# EEGbreakoutREVB.net
KiCad netlist of a schematic drawn in EAGLE
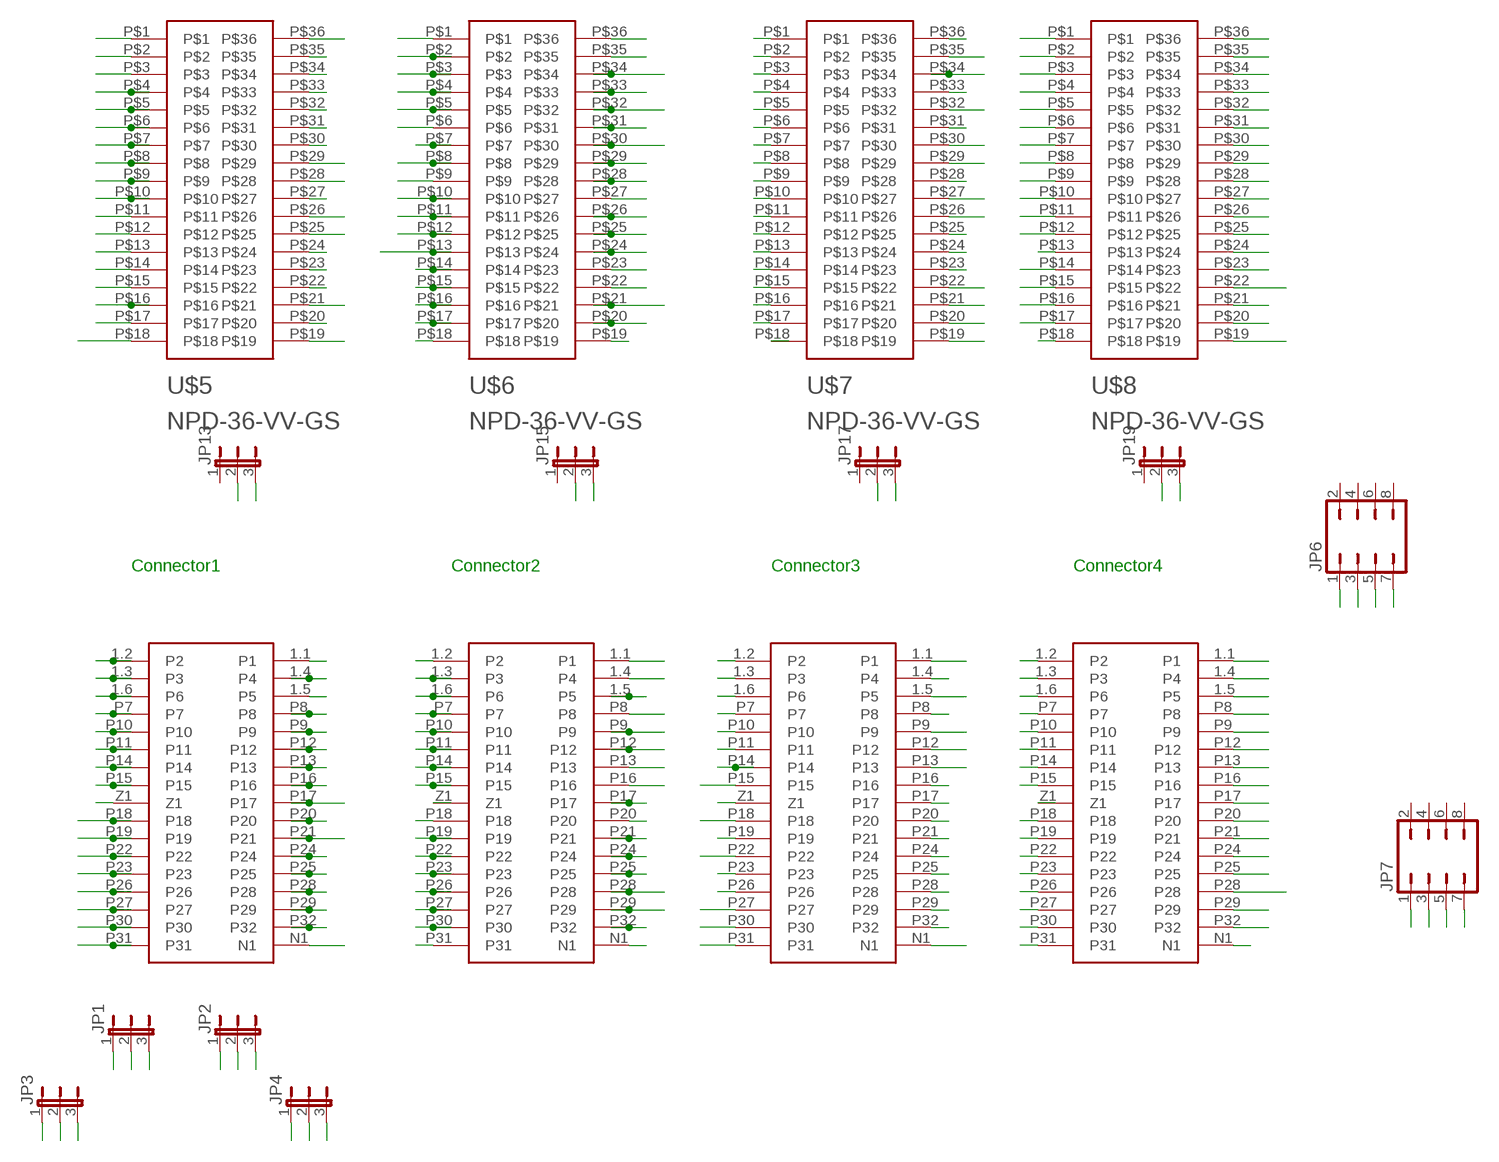
[diagram p0: schematic, sheet 1]

(export (version "E")
  (design (tool "Eeschema 10.0.6"))
  (components
    (comp (ref "JP1")
      (value "JP2E")
      (footprint "eagle-import:JP2")
      (libsource (lib "eagle-import") (part "JP2E"))
    )
    (comp (ref "JP2")
      (value "JP2E")
      (footprint "eagle-import:JP2")
      (libsource (lib "eagle-import") (part "JP2E"))
    )
    (comp (ref "JP3")
      (value "JP2E")
      (footprint "eagle-import:JP2")
      (libsource (lib "eagle-import") (part "JP2E"))
    )
    (comp (ref "JP4")
      (value "JP2E")
      (footprint "eagle-import:JP2")
      (libsource (lib "eagle-import") (part "JP2E"))
    )
    (comp (ref "JP6")
      (value "JP4Q")
      (footprint "eagle-import:JP4Q")
      (libsource (lib "eagle-import") (part "JP4Q"))
    )
    (comp (ref "JP7")
      (value "JP4Q")
      (footprint "eagle-import:JP4Q")
      (libsource (lib "eagle-import") (part "JP4Q"))
    )
    (comp (ref "JP13")
      (value "JP2E")
      (footprint "eagle-import:JP2")
      (libsource (lib "eagle-import") (part "JP2E"))
    )
    (comp (ref "JP15")
      (value "JP2E")
      (footprint "eagle-import:JP2")
      (libsource (lib "eagle-import") (part "JP2E"))
    )
    (comp (ref "JP17")
      (value "JP2E")
      (footprint "eagle-import:JP2")
      (libsource (lib "eagle-import") (part "JP2E"))
    )
    (comp (ref "JP19")
      (value "JP2E")
      (footprint "eagle-import:JP2")
      (libsource (lib "eagle-import") (part "JP2E"))
    )
    (comp (ref "U$1")
      (value "P50")
      (footprint "eagle-import:CON-MOLEX_71061-0003SM")
      (libsource (lib "eagle-import") (part "P50"))
    )
    (comp (ref "U$2")
      (value "P50")
      (footprint "eagle-import:CON-MOLEX_71061-0003SM")
      (libsource (lib "eagle-import") (part "P50"))
    )
    (comp (ref "U$3")
      (value "P50")
      (footprint "eagle-import:CON-MOLEX_71061-0003SM")
      (libsource (lib "eagle-import") (part "P50"))
    )
    (comp (ref "U$4")
      (value "P50")
      (footprint "eagle-import:CON-MOLEX_71061-0003SM")
      (libsource (lib "eagle-import") (part "P50"))
    )
    (comp (ref "U$5")
      (value "NPD-36-VV-GS")
      (footprint "eagle-import:NPD-36-VV-GS")
      (libsource (lib "eagle-import") (part "NPD-36-VV-GS"))
    )
    (comp (ref "U$6")
      (value "NPD-36-VV-GS")
      (footprint "eagle-import:NPD-36-VV-GS")
      (libsource (lib "eagle-import") (part "NPD-36-VV-GS"))
    )
    (comp (ref "U$7")
      (value "NPD-36-VV-GS")
      (footprint "eagle-import:NPD-36-VV-GS")
      (libsource (lib "eagle-import") (part "NPD-36-VV-GS"))
    )
    (comp (ref "U$8")
      (value "NPD-36-VV-GS")
      (footprint "eagle-import:NPD-36-VV-GS")
      (libsource (lib "eagle-import") (part "NPD-36-VV-GS"))
    )
  )
  (nets
    (net (code "1") (name "/1.1") (class "Default")
      (node (ref "U$1") (pin "1.1") (pinfunction "P1_1.1") (pintype "bidirectional"))
      (node (ref "U$5") (pin "P$2") (pinfunction "P$2_P$2") (pintype "bidirectional"))
    )
    (net (code "2") (name "/1.2") (class "Default")
      (node (ref "U$1") (pin "1.4") (pinfunction "P4_1.4") (pintype "bidirectional"))
      (node (ref "U$5") (pin "P$3") (pinfunction "P$3_P$3") (pintype "bidirectional"))
    )
    (net (code "3") (name "/1.3") (class "Default")
      (node (ref "U$1") (pin "1.5") (pinfunction "P5_1.5") (pintype "bidirectional"))
      (node (ref "U$5") (pin "P$4") (pinfunction "P$4_P$4") (pintype "bidirectional"))
    )
    (net (code "4") (name "/1.4") (class "Default")
      (node (ref "U$1") (pin "P8") (pinfunction "P8_P8") (pintype "bidirectional"))
      (node (ref "U$5") (pin "P$5") (pinfunction "P$5_P$5") (pintype "bidirectional"))
    )
    (net (code "5") (name "/1.5") (class "Default")
      (node (ref "U$1") (pin "P9") (pinfunction "P9_P9") (pintype "bidirectional"))
      (node (ref "U$5") (pin "P$6") (pinfunction "P$6_P$6") (pintype "bidirectional"))
    )
    (net (code "6") (name "/1.6") (class "Default")
      (node (ref "U$1") (pin "P12") (pinfunction "P12_P12") (pintype "bidirectional"))
      (node (ref "U$5") (pin "P$7") (pinfunction "P$7_P$7") (pintype "bidirectional"))
    )
    (net (code "7") (name "/1.7") (class "Default")
      (node (ref "U$1") (pin "P13") (pinfunction "P13_P13") (pintype "bidirectional"))
      (node (ref "U$5") (pin "P$8") (pinfunction "P$8_P$8") (pintype "bidirectional"))
    )
    (net (code "8") (name "/1.8") (class "Default")
      (node (ref "U$1") (pin "P16") (pinfunction "P16_P16") (pintype "bidirectional"))
      (node (ref "U$5") (pin "P$9") (pinfunction "P$9_P$9") (pintype "bidirectional"))
    )
    (net (code "9") (name "/1.9") (class "Default")
      (node (ref "U$1") (pin "P17") (pinfunction "P17_P17") (pintype "bidirectional"))
      (node (ref "U$5") (pin "P$10") (pinfunction "P$10_P$10") (pintype "bidirectional"))
    )
    (net (code "10") (name "/1.10") (class "Default")
      (node (ref "U$1") (pin "P20") (pinfunction "P20_P20") (pintype "bidirectional"))
      (node (ref "U$5") (pin "P$11") (pinfunction "P$11_P$11") (pintype "bidirectional"))
    )
    (net (code "11") (name "/1.11") (class "Default")
      (node (ref "U$1") (pin "P21") (pinfunction "P21_P21") (pintype "bidirectional"))
      (node (ref "U$5") (pin "P$12") (pinfunction "P$12_P$12") (pintype "bidirectional"))
    )
    (net (code "12") (name "/1.12") (class "Default")
      (node (ref "U$1") (pin "P24") (pinfunction "P24_P24") (pintype "bidirectional"))
      (node (ref "U$5") (pin "P$13") (pinfunction "P$13_P$13") (pintype "bidirectional"))
    )
    (net (code "13") (name "/1.13") (class "Default")
      (node (ref "U$1") (pin "P25") (pinfunction "P25_P25") (pintype "bidirectional"))
      (node (ref "U$5") (pin "P$14") (pinfunction "P$14_P$14") (pintype "bidirectional"))
    )
    (net (code "14") (name "/1.14") (class "Default")
      (node (ref "U$1") (pin "P28") (pinfunction "P28_P28") (pintype "bidirectional"))
      (node (ref "U$5") (pin "P$15") (pinfunction "P$15_P$15") (pintype "bidirectional"))
    )
    (net (code "15") (name "/1.15") (class "Default")
      (node (ref "U$1") (pin "P29") (pinfunction "P29_P29") (pintype "bidirectional"))
      (node (ref "U$5") (pin "P$16") (pinfunction "P$16_P$16") (pintype "bidirectional"))
    )
    (net (code "16") (name "/1.16") (class "Default")
      (node (ref "U$1") (pin "P32") (pinfunction "P32_P32") (pintype "bidirectional"))
      (node (ref "U$5") (pin "P$17") (pinfunction "P$17_P$17") (pintype "bidirectional"))
    )
    (net (code "17") (name "/1.17") (class "Default")
      (node (ref "U$1") (pin "1.2") (pinfunction "P2_1.2") (pintype "bidirectional"))
      (node (ref "U$5") (pin "P$20") (pinfunction "P$20_P$20") (pintype "bidirectional"))
    )
    (net (code "18") (name "/1.18") (class "Default")
      (node (ref "U$1") (pin "1.3") (pinfunction "P3_1.3") (pintype "bidirectional"))
      (node (ref "U$5") (pin "P$21") (pinfunction "P$21_P$21") (pintype "bidirectional"))
    )
    (net (code "19") (name "/1.20") (class "Default")
      (node (ref "U$1") (pin "P7") (pinfunction "P7_P7") (pintype "bidirectional"))
      (node (ref "U$5") (pin "P$23") (pinfunction "P$23_P$23") (pintype "bidirectional"))
    )
    (net (code "20") (name "/1.21") (class "Default")
      (node (ref "U$1") (pin "P10") (pinfunction "P10_P10") (pintype "bidirectional"))
      (node (ref "U$5") (pin "P$24") (pinfunction "P$24_P$24") (pintype "bidirectional"))
    )
    (net (code "21") (name "/1.22") (class "Default")
      (node (ref "U$1") (pin "P11") (pinfunction "P11_P11") (pintype "bidirectional"))
      (node (ref "U$5") (pin "P$25") (pinfunction "P$25_P$25") (pintype "bidirectional"))
    )
    (net (code "22") (name "/1.23") (class "Default")
      (node (ref "U$1") (pin "P14") (pinfunction "P14_P14") (pintype "bidirectional"))
      (node (ref "U$5") (pin "P$26") (pinfunction "P$26_P$26") (pintype "bidirectional"))
    )
    (net (code "23") (name "/1.24") (class "Default")
      (node (ref "U$1") (pin "P15") (pinfunction "P15_P15") (pintype "bidirectional"))
      (node (ref "U$5") (pin "P$27") (pinfunction "P$27_P$27") (pintype "bidirectional"))
    )
    (net (code "24") (name "/1.25") (class "Default")
      (node (ref "U$1") (pin "P18") (pinfunction "P18_P18") (pintype "bidirectional"))
      (node (ref "U$5") (pin "P$28") (pinfunction "P$28_P$28") (pintype "bidirectional"))
    )
    (net (code "25") (name "/1.26") (class "Default")
      (node (ref "U$1") (pin "P19") (pinfunction "P19_P19") (pintype "bidirectional"))
      (node (ref "U$5") (pin "P$29") (pinfunction "P$29_P$29") (pintype "bidirectional"))
    )
    (net (code "26") (name "/1.27") (class "Default")
      (node (ref "U$1") (pin "P22") (pinfunction "P22_P22") (pintype "bidirectional"))
      (node (ref "U$5") (pin "P$30") (pinfunction "P$30_P$30") (pintype "bidirectional"))
    )
    (net (code "27") (name "/1.28") (class "Default")
      (node (ref "U$1") (pin "P23") (pinfunction "P23_P23") (pintype "bidirectional"))
      (node (ref "U$5") (pin "P$31") (pinfunction "P$31_P$31") (pintype "bidirectional"))
    )
    (net (code "28") (name "/1.29") (class "Default")
      (node (ref "JP4") (pin "2") (pinfunction "2_2") (pintype "passive"))
      (node (ref "U$5") (pin "P$32") (pinfunction "P$32_P$32") (pintype "bidirectional"))
    )
    (net (code "29") (name "/1.30") (class "Default")
      (node (ref "JP2") (pin "2") (pinfunction "2_2") (pintype "passive"))
      (node (ref "U$5") (pin "P$33") (pinfunction "P$33_P$33") (pintype "bidirectional"))
    )
    (net (code "30") (name "/1.31") (class "Default")
      (node (ref "JP1") (pin "2") (pinfunction "2_2") (pintype "passive"))
      (node (ref "U$5") (pin "P$34") (pinfunction "P$34_P$34") (pintype "bidirectional"))
    )
    (net (code "31") (name "/1.32") (class "Default")
      (node (ref "JP3") (pin "2") (pinfunction "2_2") (pintype "passive"))
      (node (ref "U$5") (pin "P$35") (pinfunction "P$35_P$35") (pintype "bidirectional"))
    )
    (net (code "32") (name "/2.1") (class "Default")
      (node (ref "U$2") (pin "1.1") (pinfunction "P1_1.1") (pintype "bidirectional"))
      (node (ref "U$6") (pin "P$2") (pinfunction "P$2_P$2") (pintype "bidirectional"))
    )
    (net (code "33") (name "/2.2") (class "Default")
      (node (ref "U$2") (pin "1.4") (pinfunction "P4_1.4") (pintype "bidirectional"))
      (node (ref "U$6") (pin "P$3") (pinfunction "P$3_P$3") (pintype "bidirectional"))
    )
    (net (code "34") (name "/2.3") (class "Default")
      (node (ref "U$2") (pin "1.5") (pinfunction "P5_1.5") (pintype "bidirectional"))
      (node (ref "U$6") (pin "P$4") (pinfunction "P$4_P$4") (pintype "bidirectional"))
    )
    (net (code "35") (name "/2.4") (class "Default")
      (node (ref "U$2") (pin "P8") (pinfunction "P8_P8") (pintype "bidirectional"))
      (node (ref "U$6") (pin "P$5") (pinfunction "P$5_P$5") (pintype "bidirectional"))
    )
    (net (code "36") (name "/2.5") (class "Default")
      (node (ref "U$2") (pin "P9") (pinfunction "P9_P9") (pintype "bidirectional"))
      (node (ref "U$6") (pin "P$6") (pinfunction "P$6_P$6") (pintype "bidirectional"))
    )
    (net (code "37") (name "/2.6") (class "Default")
      (node (ref "U$2") (pin "P12") (pinfunction "P12_P12") (pintype "bidirectional"))
      (node (ref "U$6") (pin "P$7") (pinfunction "P$7_P$7") (pintype "bidirectional"))
    )
    (net (code "38") (name "/2.7") (class "Default")
      (node (ref "U$2") (pin "P13") (pinfunction "P13_P13") (pintype "bidirectional"))
      (node (ref "U$6") (pin "P$8") (pinfunction "P$8_P$8") (pintype "bidirectional"))
    )
    (net (code "39") (name "/2.8") (class "Default")
      (node (ref "U$2") (pin "P16") (pinfunction "P16_P16") (pintype "bidirectional"))
      (node (ref "U$6") (pin "P$9") (pinfunction "P$9_P$9") (pintype "bidirectional"))
    )
    (net (code "40") (name "/2.9") (class "Default")
      (node (ref "U$2") (pin "P17") (pinfunction "P17_P17") (pintype "bidirectional"))
      (node (ref "U$6") (pin "P$10") (pinfunction "P$10_P$10") (pintype "bidirectional"))
    )
    (net (code "41") (name "/2.10") (class "Default")
      (node (ref "U$2") (pin "P20") (pinfunction "P20_P20") (pintype "bidirectional"))
      (node (ref "U$6") (pin "P$11") (pinfunction "P$11_P$11") (pintype "bidirectional"))
    )
    (net (code "42") (name "/2.11") (class "Default")
      (node (ref "U$2") (pin "P21") (pinfunction "P21_P21") (pintype "bidirectional"))
      (node (ref "U$6") (pin "P$12") (pinfunction "P$12_P$12") (pintype "bidirectional"))
    )
    (net (code "43") (name "/2.12") (class "Default")
      (node (ref "U$2") (pin "P24") (pinfunction "P24_P24") (pintype "bidirectional"))
      (node (ref "U$6") (pin "P$13") (pinfunction "P$13_P$13") (pintype "bidirectional"))
    )
    (net (code "44") (name "/2.13") (class "Default")
      (node (ref "U$2") (pin "P25") (pinfunction "P25_P25") (pintype "bidirectional"))
      (node (ref "U$6") (pin "P$14") (pinfunction "P$14_P$14") (pintype "bidirectional"))
    )
    (net (code "45") (name "/2.14") (class "Default")
      (node (ref "U$2") (pin "P28") (pinfunction "P28_P28") (pintype "bidirectional"))
      (node (ref "U$6") (pin "P$15") (pinfunction "P$15_P$15") (pintype "bidirectional"))
    )
    (net (code "46") (name "/2.15") (class "Default")
      (node (ref "U$2") (pin "P29") (pinfunction "P29_P29") (pintype "bidirectional"))
      (node (ref "U$6") (pin "P$16") (pinfunction "P$16_P$16") (pintype "bidirectional"))
    )
    (net (code "47") (name "/2.16") (class "Default")
      (node (ref "U$2") (pin "P32") (pinfunction "P32_P32") (pintype "bidirectional"))
      (node (ref "U$6") (pin "P$17") (pinfunction "P$17_P$17") (pintype "bidirectional"))
    )
    (net (code "48") (name "/2.17") (class "Default")
      (node (ref "U$2") (pin "1.2") (pinfunction "P2_1.2") (pintype "bidirectional"))
      (node (ref "U$6") (pin "P$20") (pinfunction "P$20_P$20") (pintype "bidirectional"))
    )
    (net (code "49") (name "/2.18") (class "Default")
      (node (ref "U$2") (pin "1.3") (pinfunction "P3_1.3") (pintype "bidirectional"))
      (node (ref "U$6") (pin "P$21") (pinfunction "P$21_P$21") (pintype "bidirectional"))
    )
    (net (code "50") (name "/2.19") (class "Default")
      (node (ref "U$2") (pin "1.6") (pinfunction "P6_1.6") (pintype "bidirectional"))
      (node (ref "U$6") (pin "P$22") (pinfunction "P$22_P$22") (pintype "bidirectional"))
    )
    (net (code "51") (name "/2.20") (class "Default")
      (node (ref "U$2") (pin "P7") (pinfunction "P7_P7") (pintype "bidirectional"))
      (node (ref "U$6") (pin "P$23") (pinfunction "P$23_P$23") (pintype "bidirectional"))
    )
    (net (code "52") (name "/2.21") (class "Default")
      (node (ref "U$2") (pin "P10") (pinfunction "P10_P10") (pintype "bidirectional"))
      (node (ref "U$6") (pin "P$24") (pinfunction "P$24_P$24") (pintype "bidirectional"))
    )
    (net (code "53") (name "/2.22") (class "Default")
      (node (ref "U$2") (pin "P11") (pinfunction "P11_P11") (pintype "bidirectional"))
      (node (ref "U$6") (pin "P$25") (pinfunction "P$25_P$25") (pintype "bidirectional"))
    )
    (net (code "54") (name "/2.23") (class "Default")
      (node (ref "U$2") (pin "P14") (pinfunction "P14_P14") (pintype "bidirectional"))
      (node (ref "U$6") (pin "P$26") (pinfunction "P$26_P$26") (pintype "bidirectional"))
    )
    (net (code "55") (name "/2.24") (class "Default")
      (node (ref "U$2") (pin "P15") (pinfunction "P15_P15") (pintype "bidirectional"))
      (node (ref "U$6") (pin "P$27") (pinfunction "P$27_P$27") (pintype "bidirectional"))
    )
    (net (code "56") (name "/2.25") (class "Default")
      (node (ref "U$2") (pin "P18") (pinfunction "P18_P18") (pintype "bidirectional"))
      (node (ref "U$6") (pin "P$28") (pinfunction "P$28_P$28") (pintype "bidirectional"))
    )
    (net (code "57") (name "/2.26") (class "Default")
      (node (ref "U$2") (pin "P19") (pinfunction "P19_P19") (pintype "bidirectional"))
      (node (ref "U$6") (pin "P$29") (pinfunction "P$29_P$29") (pintype "bidirectional"))
    )
    (net (code "58") (name "/2.27") (class "Default")
      (node (ref "U$2") (pin "P22") (pinfunction "P22_P22") (pintype "bidirectional"))
      (node (ref "U$6") (pin "P$30") (pinfunction "P$30_P$30") (pintype "bidirectional"))
    )
    (net (code "59") (name "/2.28") (class "Default")
      (node (ref "U$2") (pin "P23") (pinfunction "P23_P23") (pintype "bidirectional"))
      (node (ref "U$6") (pin "P$31") (pinfunction "P$31_P$31") (pintype "bidirectional"))
    )
    (net (code "60") (name "/2.29") (class "Default")
      (node (ref "U$2") (pin "P26") (pinfunction "P26_P26") (pintype "bidirectional"))
      (node (ref "U$6") (pin "P$32") (pinfunction "P$32_P$32") (pintype "bidirectional"))
    )
    (net (code "61") (name "/2.30") (class "Default")
      (node (ref "U$2") (pin "P27") (pinfunction "P27_P27") (pintype "bidirectional"))
      (node (ref "U$6") (pin "P$33") (pinfunction "P$33_P$33") (pintype "bidirectional"))
    )
    (net (code "62") (name "/2.31") (class "Default")
      (node (ref "U$2") (pin "P30") (pinfunction "P30_P30") (pintype "bidirectional"))
      (node (ref "U$6") (pin "P$34") (pinfunction "P$34_P$34") (pintype "bidirectional"))
    )
    (net (code "63") (name "/2.32") (class "Default")
      (node (ref "U$2") (pin "P31") (pinfunction "P31_P31") (pintype "bidirectional"))
      (node (ref "U$6") (pin "P$35") (pinfunction "P$35_P$35") (pintype "bidirectional"))
    )
    (net (code "64") (name "/3.1") (class "Default")
      (node (ref "U$3") (pin "1.1") (pinfunction "P1_1.1") (pintype "bidirectional"))
      (node (ref "U$7") (pin "P$2") (pinfunction "P$2_P$2") (pintype "bidirectional"))
    )
    (net (code "65") (name "/3.2") (class "Default")
      (node (ref "U$3") (pin "1.4") (pinfunction "P4_1.4") (pintype "bidirectional"))
      (node (ref "U$7") (pin "P$3") (pinfunction "P$3_P$3") (pintype "bidirectional"))
    )
    (net (code "66") (name "/3.3") (class "Default")
      (node (ref "U$3") (pin "1.5") (pinfunction "P5_1.5") (pintype "bidirectional"))
      (node (ref "U$7") (pin "P$4") (pinfunction "P$4_P$4") (pintype "bidirectional"))
    )
    (net (code "67") (name "/3.4") (class "Default")
      (node (ref "U$3") (pin "P8") (pinfunction "P8_P8") (pintype "bidirectional"))
      (node (ref "U$7") (pin "P$5") (pinfunction "P$5_P$5") (pintype "bidirectional"))
    )
    (net (code "68") (name "/3.5") (class "Default")
      (node (ref "U$3") (pin "P9") (pinfunction "P9_P9") (pintype "bidirectional"))
      (node (ref "U$7") (pin "P$6") (pinfunction "P$6_P$6") (pintype "bidirectional"))
    )
    (net (code "69") (name "/3.6") (class "Default")
      (node (ref "U$3") (pin "P12") (pinfunction "P12_P12") (pintype "bidirectional"))
      (node (ref "U$7") (pin "P$7") (pinfunction "P$7_P$7") (pintype "bidirectional"))
    )
    (net (code "70") (name "/3.7") (class "Default")
      (node (ref "U$3") (pin "P13") (pinfunction "P13_P13") (pintype "bidirectional"))
      (node (ref "U$7") (pin "P$8") (pinfunction "P$8_P$8") (pintype "bidirectional"))
    )
    (net (code "71") (name "/3.8") (class "Default")
      (node (ref "U$3") (pin "P16") (pinfunction "P16_P16") (pintype "bidirectional"))
      (node (ref "U$7") (pin "P$9") (pinfunction "P$9_P$9") (pintype "bidirectional"))
    )
    (net (code "72") (name "/3.9") (class "Default")
      (node (ref "U$3") (pin "P17") (pinfunction "P17_P17") (pintype "bidirectional"))
      (node (ref "U$7") (pin "P$10") (pinfunction "P$10_P$10") (pintype "bidirectional"))
    )
    (net (code "73") (name "/3.10") (class "Default")
      (node (ref "U$3") (pin "P20") (pinfunction "P20_P20") (pintype "bidirectional"))
      (node (ref "U$7") (pin "P$11") (pinfunction "P$11_P$11") (pintype "bidirectional"))
    )
    (net (code "74") (name "/3.11") (class "Default")
      (node (ref "U$3") (pin "P21") (pinfunction "P21_P21") (pintype "bidirectional"))
      (node (ref "U$7") (pin "P$12") (pinfunction "P$12_P$12") (pintype "bidirectional"))
    )
    (net (code "75") (name "/3.12") (class "Default")
      (node (ref "U$3") (pin "P24") (pinfunction "P24_P24") (pintype "bidirectional"))
      (node (ref "U$7") (pin "P$13") (pinfunction "P$13_P$13") (pintype "bidirectional"))
    )
    (net (code "76") (name "/3.13") (class "Default")
      (node (ref "U$3") (pin "P25") (pinfunction "P25_P25") (pintype "bidirectional"))
      (node (ref "U$7") (pin "P$14") (pinfunction "P$14_P$14") (pintype "bidirectional"))
    )
    (net (code "77") (name "/3.14") (class "Default")
      (node (ref "U$3") (pin "P28") (pinfunction "P28_P28") (pintype "bidirectional"))
      (node (ref "U$7") (pin "P$15") (pinfunction "P$15_P$15") (pintype "bidirectional"))
    )
    (net (code "78") (name "/3.15") (class "Default")
      (node (ref "U$3") (pin "P29") (pinfunction "P29_P29") (pintype "bidirectional"))
      (node (ref "U$7") (pin "P$16") (pinfunction "P$16_P$16") (pintype "bidirectional"))
    )
    (net (code "79") (name "/3.16") (class "Default")
      (node (ref "U$3") (pin "P32") (pinfunction "P32_P32") (pintype "bidirectional"))
      (node (ref "U$7") (pin "P$17") (pinfunction "P$17_P$17") (pintype "bidirectional"))
    )
    (net (code "80") (name "/3.17") (class "Default")
      (node (ref "U$3") (pin "1.2") (pinfunction "P2_1.2") (pintype "bidirectional"))
      (node (ref "U$7") (pin "P$20") (pinfunction "P$20_P$20") (pintype "bidirectional"))
    )
    (net (code "81") (name "/3.18") (class "Default")
      (node (ref "U$3") (pin "1.3") (pinfunction "P3_1.3") (pintype "bidirectional"))
      (node (ref "U$7") (pin "P$21") (pinfunction "P$21_P$21") (pintype "bidirectional"))
    )
    (net (code "82") (name "/3.19") (class "Default")
      (node (ref "U$3") (pin "1.6") (pinfunction "P6_1.6") (pintype "bidirectional"))
      (node (ref "U$7") (pin "P$22") (pinfunction "P$22_P$22") (pintype "bidirectional"))
    )
    (net (code "83") (name "/3.20") (class "Default")
      (node (ref "U$3") (pin "P7") (pinfunction "P7_P7") (pintype "bidirectional"))
      (node (ref "U$7") (pin "P$23") (pinfunction "P$23_P$23") (pintype "bidirectional"))
    )
    (net (code "84") (name "/3.21") (class "Default")
      (node (ref "U$3") (pin "P10") (pinfunction "P10_P10") (pintype "bidirectional"))
      (node (ref "U$7") (pin "P$24") (pinfunction "P$24_P$24") (pintype "bidirectional"))
    )
    (net (code "85") (name "/3.22") (class "Default")
      (node (ref "U$3") (pin "P11") (pinfunction "P11_P11") (pintype "bidirectional"))
      (node (ref "U$7") (pin "P$25") (pinfunction "P$25_P$25") (pintype "bidirectional"))
    )
    (net (code "86") (name "/3.23") (class "Default")
      (node (ref "U$3") (pin "P14") (pinfunction "P14_P14") (pintype "bidirectional"))
      (node (ref "U$7") (pin "P$26") (pinfunction "P$26_P$26") (pintype "bidirectional"))
    )
    (net (code "87") (name "/3.24") (class "Default")
      (node (ref "U$3") (pin "P15") (pinfunction "P15_P15") (pintype "bidirectional"))
      (node (ref "U$7") (pin "P$27") (pinfunction "P$27_P$27") (pintype "bidirectional"))
    )
    (net (code "88") (name "/3.25") (class "Default")
      (node (ref "U$3") (pin "P18") (pinfunction "P18_P18") (pintype "bidirectional"))
      (node (ref "U$7") (pin "P$28") (pinfunction "P$28_P$28") (pintype "bidirectional"))
    )
    (net (code "89") (name "/3.26") (class "Default")
      (node (ref "U$3") (pin "P19") (pinfunction "P19_P19") (pintype "bidirectional"))
      (node (ref "U$7") (pin "P$29") (pinfunction "P$29_P$29") (pintype "bidirectional"))
    )
    (net (code "90") (name "/3.27") (class "Default")
      (node (ref "U$3") (pin "P22") (pinfunction "P22_P22") (pintype "bidirectional"))
      (node (ref "U$7") (pin "P$30") (pinfunction "P$30_P$30") (pintype "bidirectional"))
    )
    (net (code "91") (name "/3.28") (class "Default")
      (node (ref "U$3") (pin "P23") (pinfunction "P23_P23") (pintype "bidirectional"))
      (node (ref "U$7") (pin "P$31") (pinfunction "P$31_P$31") (pintype "bidirectional"))
    )
    (net (code "92") (name "/3.29") (class "Default")
      (node (ref "U$3") (pin "P26") (pinfunction "P26_P26") (pintype "bidirectional"))
      (node (ref "U$7") (pin "P$32") (pinfunction "P$32_P$32") (pintype "bidirectional"))
    )
    (net (code "93") (name "/3.30") (class "Default")
      (node (ref "U$3") (pin "P27") (pinfunction "P27_P27") (pintype "bidirectional"))
      (node (ref "U$7") (pin "P$33") (pinfunction "P$33_P$33") (pintype "bidirectional"))
    )
    (net (code "94") (name "/3.31") (class "Default")
      (node (ref "U$3") (pin "P30") (pinfunction "P30_P30") (pintype "bidirectional"))
      (node (ref "U$7") (pin "P$34") (pinfunction "P$34_P$34") (pintype "bidirectional"))
    )
    (net (code "95") (name "/3.32") (class "Default")
      (node (ref "U$3") (pin "P31") (pinfunction "P31_P31") (pintype "bidirectional"))
      (node (ref "U$7") (pin "P$35") (pinfunction "P$35_P$35") (pintype "bidirectional"))
    )
    (net (code "96") (name "/4.1") (class "Default")
      (node (ref "U$4") (pin "1.1") (pinfunction "P1_1.1") (pintype "bidirectional"))
      (node (ref "U$8") (pin "P$2") (pinfunction "P$2_P$2") (pintype "bidirectional"))
    )
    (net (code "97") (name "/4.2") (class "Default")
      (node (ref "U$4") (pin "1.4") (pinfunction "P4_1.4") (pintype "bidirectional"))
      (node (ref "U$8") (pin "P$3") (pinfunction "P$3_P$3") (pintype "bidirectional"))
    )
    (net (code "98") (name "/4.3") (class "Default")
      (node (ref "U$4") (pin "1.5") (pinfunction "P5_1.5") (pintype "bidirectional"))
      (node (ref "U$8") (pin "P$4") (pinfunction "P$4_P$4") (pintype "bidirectional"))
    )
    (net (code "99") (name "/4.4") (class "Default")
      (node (ref "U$4") (pin "P8") (pinfunction "P8_P8") (pintype "bidirectional"))
      (node (ref "U$8") (pin "P$5") (pinfunction "P$5_P$5") (pintype "bidirectional"))
    )
    (net (code "100") (name "/4.5") (class "Default")
      (node (ref "U$4") (pin "P9") (pinfunction "P9_P9") (pintype "bidirectional"))
      (node (ref "U$8") (pin "P$6") (pinfunction "P$6_P$6") (pintype "bidirectional"))
    )
    (net (code "101") (name "/4.6") (class "Default")
      (node (ref "U$4") (pin "P12") (pinfunction "P12_P12") (pintype "bidirectional"))
      (node (ref "U$8") (pin "P$7") (pinfunction "P$7_P$7") (pintype "bidirectional"))
    )
    (net (code "102") (name "/4.7") (class "Default")
      (node (ref "U$4") (pin "P13") (pinfunction "P13_P13") (pintype "bidirectional"))
      (node (ref "U$8") (pin "P$8") (pinfunction "P$8_P$8") (pintype "bidirectional"))
    )
    (net (code "103") (name "/4.8") (class "Default")
      (node (ref "U$4") (pin "P16") (pinfunction "P16_P16") (pintype "bidirectional"))
      (node (ref "U$8") (pin "P$9") (pinfunction "P$9_P$9") (pintype "bidirectional"))
    )
    (net (code "104") (name "/4.9") (class "Default")
      (node (ref "U$4") (pin "P17") (pinfunction "P17_P17") (pintype "bidirectional"))
      (node (ref "U$8") (pin "P$10") (pinfunction "P$10_P$10") (pintype "bidirectional"))
    )
    (net (code "105") (name "/4.10") (class "Default")
      (node (ref "U$4") (pin "P20") (pinfunction "P20_P20") (pintype "bidirectional"))
      (node (ref "U$8") (pin "P$11") (pinfunction "P$11_P$11") (pintype "bidirectional"))
    )
    (net (code "106") (name "/4.11") (class "Default")
      (node (ref "U$4") (pin "P21") (pinfunction "P21_P21") (pintype "bidirectional"))
      (node (ref "U$8") (pin "P$12") (pinfunction "P$12_P$12") (pintype "bidirectional"))
    )
    (net (code "107") (name "/4.12") (class "Default")
      (node (ref "U$4") (pin "P24") (pinfunction "P24_P24") (pintype "bidirectional"))
      (node (ref "U$8") (pin "P$13") (pinfunction "P$13_P$13") (pintype "bidirectional"))
    )
    (net (code "108") (name "/4.13") (class "Default")
      (node (ref "U$4") (pin "P25") (pinfunction "P25_P25") (pintype "bidirectional"))
      (node (ref "U$8") (pin "P$14") (pinfunction "P$14_P$14") (pintype "bidirectional"))
    )
    (net (code "109") (name "/4.14") (class "Default")
      (node (ref "U$4") (pin "P28") (pinfunction "P28_P28") (pintype "bidirectional"))
      (node (ref "U$8") (pin "P$15") (pinfunction "P$15_P$15") (pintype "bidirectional"))
    )
    (net (code "110") (name "/4.15") (class "Default")
      (node (ref "U$4") (pin "P29") (pinfunction "P29_P29") (pintype "bidirectional"))
      (node (ref "U$8") (pin "P$16") (pinfunction "P$16_P$16") (pintype "bidirectional"))
    )
    (net (code "111") (name "/4.16") (class "Default")
      (node (ref "U$4") (pin "P32") (pinfunction "P32_P32") (pintype "bidirectional"))
      (node (ref "U$8") (pin "P$17") (pinfunction "P$17_P$17") (pintype "bidirectional"))
    )
    (net (code "112") (name "/4.17") (class "Default")
      (node (ref "U$4") (pin "1.2") (pinfunction "P2_1.2") (pintype "bidirectional"))
      (node (ref "U$8") (pin "P$20") (pinfunction "P$20_P$20") (pintype "bidirectional"))
    )
    (net (code "113") (name "/4.18") (class "Default")
      (node (ref "U$4") (pin "1.3") (pinfunction "P3_1.3") (pintype "bidirectional"))
      (node (ref "U$8") (pin "P$21") (pinfunction "P$21_P$21") (pintype "bidirectional"))
    )
    (net (code "114") (name "/4.19") (class "Default")
      (node (ref "U$4") (pin "1.6") (pinfunction "P6_1.6") (pintype "bidirectional"))
      (node (ref "U$8") (pin "P$22") (pinfunction "P$22_P$22") (pintype "bidirectional"))
    )
    (net (code "115") (name "/4.20") (class "Default")
      (node (ref "U$4") (pin "P7") (pinfunction "P7_P7") (pintype "bidirectional"))
      (node (ref "U$8") (pin "P$23") (pinfunction "P$23_P$23") (pintype "bidirectional"))
    )
    (net (code "116") (name "/4.21") (class "Default")
      (node (ref "U$4") (pin "P10") (pinfunction "P10_P10") (pintype "bidirectional"))
      (node (ref "U$8") (pin "P$24") (pinfunction "P$24_P$24") (pintype "bidirectional"))
    )
    (net (code "117") (name "/4.22") (class "Default")
      (node (ref "U$4") (pin "P11") (pinfunction "P11_P11") (pintype "bidirectional"))
      (node (ref "U$8") (pin "P$25") (pinfunction "P$25_P$25") (pintype "bidirectional"))
    )
    (net (code "118") (name "/4.23") (class "Default")
      (node (ref "U$4") (pin "P14") (pinfunction "P14_P14") (pintype "bidirectional"))
      (node (ref "U$8") (pin "P$26") (pinfunction "P$26_P$26") (pintype "bidirectional"))
    )
    (net (code "119") (name "/4.24") (class "Default")
      (node (ref "U$4") (pin "P15") (pinfunction "P15_P15") (pintype "bidirectional"))
      (node (ref "U$8") (pin "P$27") (pinfunction "P$27_P$27") (pintype "bidirectional"))
    )
    (net (code "120") (name "/4.25") (class "Default")
      (node (ref "U$4") (pin "P18") (pinfunction "P18_P18") (pintype "bidirectional"))
      (node (ref "U$8") (pin "P$28") (pinfunction "P$28_P$28") (pintype "bidirectional"))
    )
    (net (code "121") (name "/4.26") (class "Default")
      (node (ref "U$4") (pin "P19") (pinfunction "P19_P19") (pintype "bidirectional"))
      (node (ref "U$8") (pin "P$29") (pinfunction "P$29_P$29") (pintype "bidirectional"))
    )
    (net (code "122") (name "/4.27") (class "Default")
      (node (ref "U$4") (pin "P22") (pinfunction "P22_P22") (pintype "bidirectional"))
      (node (ref "U$8") (pin "P$30") (pinfunction "P$30_P$30") (pintype "bidirectional"))
    )
    (net (code "123") (name "/4.28") (class "Default")
      (node (ref "U$4") (pin "P23") (pinfunction "P23_P23") (pintype "bidirectional"))
      (node (ref "U$8") (pin "P$31") (pinfunction "P$31_P$31") (pintype "bidirectional"))
    )
    (net (code "124") (name "/4.29") (class "Default")
      (node (ref "U$4") (pin "P26") (pinfunction "P26_P26") (pintype "bidirectional"))
      (node (ref "U$8") (pin "P$32") (pinfunction "P$32_P$32") (pintype "bidirectional"))
    )
    (net (code "125") (name "/4.30") (class "Default")
      (node (ref "U$4") (pin "P27") (pinfunction "P27_P27") (pintype "bidirectional"))
      (node (ref "U$8") (pin "P$33") (pinfunction "P$33_P$33") (pintype "bidirectional"))
    )
    (net (code "126") (name "/4.31") (class "Default")
      (node (ref "U$4") (pin "P30") (pinfunction "P30_P30") (pintype "bidirectional"))
      (node (ref "U$8") (pin "P$34") (pinfunction "P$34_P$34") (pintype "bidirectional"))
    )
    (net (code "127") (name "/4.32") (class "Default")
      (node (ref "U$4") (pin "P31") (pinfunction "P31_P31") (pintype "bidirectional"))
      (node (ref "U$8") (pin "P$35") (pinfunction "P$35_P$35") (pintype "bidirectional"))
    )
    (net (code "128") (name "/C1.29") (class "Default")
      (node (ref "JP4") (pin "1") (pinfunction "1_1") (pintype "passive"))
      (node (ref "U$1") (pin "P26") (pinfunction "P26_P26") (pintype "bidirectional"))
    )
    (net (code "129") (name "/C1.30") (class "Default")
      (node (ref "JP2") (pin "1") (pinfunction "1_1") (pintype "passive"))
      (node (ref "U$1") (pin "P27") (pinfunction "P27_P27") (pintype "bidirectional"))
    )
    (net (code "130") (name "/C1.31") (class "Default")
      (node (ref "JP1") (pin "1") (pinfunction "1_1") (pintype "passive"))
      (node (ref "U$1") (pin "P30") (pinfunction "P30_P30") (pintype "bidirectional"))
    )
    (net (code "131") (name "/C1.32") (class "Default")
      (node (ref "JP3") (pin "1") (pinfunction "1_1") (pintype "passive"))
      (node (ref "U$1") (pin "P31") (pinfunction "P31_P31") (pintype "bidirectional"))
    )
    (net (code "132") (name "/GND") (class "Default")
      (node (ref "JP13") (pin "3") (pinfunction "3_3") (pintype "passive"))
      (node (ref "JP15") (pin "3") (pinfunction "3_3") (pintype "passive"))
      (node (ref "JP17") (pin "3") (pinfunction "3_3") (pintype "passive"))
      (node (ref "JP19") (pin "3") (pinfunction "3_3") (pintype "passive"))
      (node (ref "U$1") (pin "N1") (pinfunction "N1_N1") (pintype "bidirectional"))
      (node (ref "U$2") (pin "N1") (pinfunction "N1_N1") (pintype "bidirectional"))
      (node (ref "U$3") (pin "N1") (pinfunction "N1_N1") (pintype "bidirectional"))
      (node (ref "U$4") (pin "N1") (pinfunction "N1_N1") (pintype "bidirectional"))
      (node (ref "U$5") (pin "P$1") (pinfunction "P$1_P$1") (pintype "bidirectional"))
      (node (ref "U$5") (pin "P$19") (pinfunction "P$19_P$19") (pintype "bidirectional"))
      (node (ref "U$6") (pin "P$1") (pinfunction "P$1_P$1") (pintype "bidirectional"))
      (node (ref "U$6") (pin "P$19") (pinfunction "P$19_P$19") (pintype "bidirectional"))
      (node (ref "U$7") (pin "P$1") (pinfunction "P$1_P$1") (pintype "bidirectional"))
      (node (ref "U$7") (pin "P$19") (pinfunction "P$19_P$19") (pintype "bidirectional"))
      (node (ref "U$8") (pin "P$1") (pinfunction "P$1_P$1") (pintype "bidirectional"))
      (node (ref "U$8") (pin "P$19") (pinfunction "P$19_P$19") (pintype "bidirectional"))
    )
    (net (code "133") (name "/J29") (class "Default")
      (node (ref "JP4") (pin "3") (pinfunction "3_3") (pintype "passive"))
      (node (ref "JP6") (pin "1") (pinfunction "1_1") (pintype "passive"))
    )
    (net (code "134") (name "/J30") (class "Default")
      (node (ref "JP2") (pin "3") (pinfunction "3_3") (pintype "passive"))
      (node (ref "JP6") (pin "3") (pinfunction "3_3") (pintype "passive"))
    )
    (net (code "135") (name "/J31") (class "Default")
      (node (ref "JP1") (pin "3") (pinfunction "3_3") (pintype "passive"))
      (node (ref "JP6") (pin "5") (pinfunction "5_5") (pintype "passive"))
    )
    (net (code "136") (name "/J32") (class "Default")
      (node (ref "JP3") (pin "3") (pinfunction "3_3") (pintype "passive"))
      (node (ref "JP6") (pin "7") (pinfunction "7_7") (pintype "passive"))
    )
    (net (code "137") (name "/N$10") (class "Default")
      (node (ref "U$1") (pin "1.6") (pinfunction "P6_1.6") (pintype "bidirectional"))
      (node (ref "U$5") (pin "P$22") (pinfunction "P$22_P$22") (pintype "bidirectional"))
    )
    (net (code "138") (name "/REF") (class "Default")
      (node (ref "JP13") (pin "2") (pinfunction "2_2") (pintype "passive"))
      (node (ref "JP7") (pin "1") (pinfunction "1_1") (pintype "passive"))
      (node (ref "U$1") (pin "Z1") (pinfunction "Z1_Z1") (pintype "bidirectional"))
      (node (ref "U$5") (pin "P$18") (pinfunction "P$18_P$18") (pintype "bidirectional"))
      (node (ref "U$5") (pin "P$36") (pinfunction "P$36_P$36") (pintype "bidirectional"))
    )
    (net (code "139") (name "/REF1") (class "Default")
      (node (ref "JP15") (pin "2") (pinfunction "2_2") (pintype "passive"))
      (node (ref "JP7") (pin "3") (pinfunction "3_3") (pintype "passive"))
      (node (ref "U$2") (pin "Z1") (pinfunction "Z1_Z1") (pintype "bidirectional"))
      (node (ref "U$6") (pin "P$18") (pinfunction "P$18_P$18") (pintype "bidirectional"))
      (node (ref "U$6") (pin "P$36") (pinfunction "P$36_P$36") (pintype "bidirectional"))
    )
    (net (code "140") (name "/REF2") (class "Default")
      (node (ref "JP17") (pin "2") (pinfunction "2_2") (pintype "passive"))
      (node (ref "JP7") (pin "5") (pinfunction "5_5") (pintype "passive"))
      (node (ref "U$3") (pin "Z1") (pinfunction "Z1_Z1") (pintype "bidirectional"))
      (node (ref "U$7") (pin "P$18") (pinfunction "P$18_P$18") (pintype "bidirectional"))
      (node (ref "U$7") (pin "P$36") (pinfunction "P$36_P$36") (pintype "bidirectional"))
    )
    (net (code "141") (name "/REF3") (class "Default")
      (node (ref "JP19") (pin "2") (pinfunction "2_2") (pintype "passive"))
      (node (ref "JP7") (pin "7") (pinfunction "7_7") (pintype "passive"))
      (node (ref "U$4") (pin "Z1") (pinfunction "Z1_Z1") (pintype "bidirectional"))
      (node (ref "U$8") (pin "P$18") (pinfunction "P$18_P$18") (pintype "bidirectional"))
      (node (ref "U$8") (pin "P$36") (pinfunction "P$36_P$36") (pintype "bidirectional"))
    )
    (net (code "142") (name "unconnected-(JP6-Pad2)") (class "Default")
      (node (ref "JP6") (pin "2") (pinfunction "2_2") (pintype "passive"))
    )
    (net (code "143") (name "unconnected-(JP6-Pad4)") (class "Default")
      (node (ref "JP6") (pin "4") (pinfunction "4_4") (pintype "passive"))
    )
    (net (code "144") (name "unconnected-(JP6-Pad6)") (class "Default")
      (node (ref "JP6") (pin "6") (pinfunction "6_6") (pintype "passive"))
    )
    (net (code "145") (name "unconnected-(JP6-Pad8)") (class "Default")
      (node (ref "JP6") (pin "8") (pinfunction "8_8") (pintype "passive"))
    )
    (net (code "146") (name "unconnected-(JP7-Pad2)") (class "Default")
      (node (ref "JP7") (pin "2") (pinfunction "2_2") (pintype "passive"))
    )
    (net (code "147") (name "unconnected-(JP7-Pad4)") (class "Default")
      (node (ref "JP7") (pin "4") (pinfunction "4_4") (pintype "passive"))
    )
    (net (code "148") (name "unconnected-(JP7-Pad6)") (class "Default")
      (node (ref "JP7") (pin "6") (pinfunction "6_6") (pintype "passive"))
    )
    (net (code "149") (name "unconnected-(JP7-Pad8)") (class "Default")
      (node (ref "JP7") (pin "8") (pinfunction "8_8") (pintype "passive"))
    )
    (net (code "150") (name "unconnected-(JP13-Pad1)") (class "Default")
      (node (ref "JP13") (pin "1") (pinfunction "1_1") (pintype "passive"))
    )
    (net (code "151") (name "unconnected-(JP15-Pad1)") (class "Default")
      (node (ref "JP15") (pin "1") (pinfunction "1_1") (pintype "passive"))
    )
    (net (code "152") (name "unconnected-(JP17-Pad1)") (class "Default")
      (node (ref "JP17") (pin "1") (pinfunction "1_1") (pintype "passive"))
    )
    (net (code "153") (name "unconnected-(JP19-Pad1)") (class "Default")
      (node (ref "JP19") (pin "1") (pinfunction "1_1") (pintype "passive"))
    )
  )
)
